# FPGA_SYSTERM.net
KiCad netlist of a schematic drawn in Altium Designer
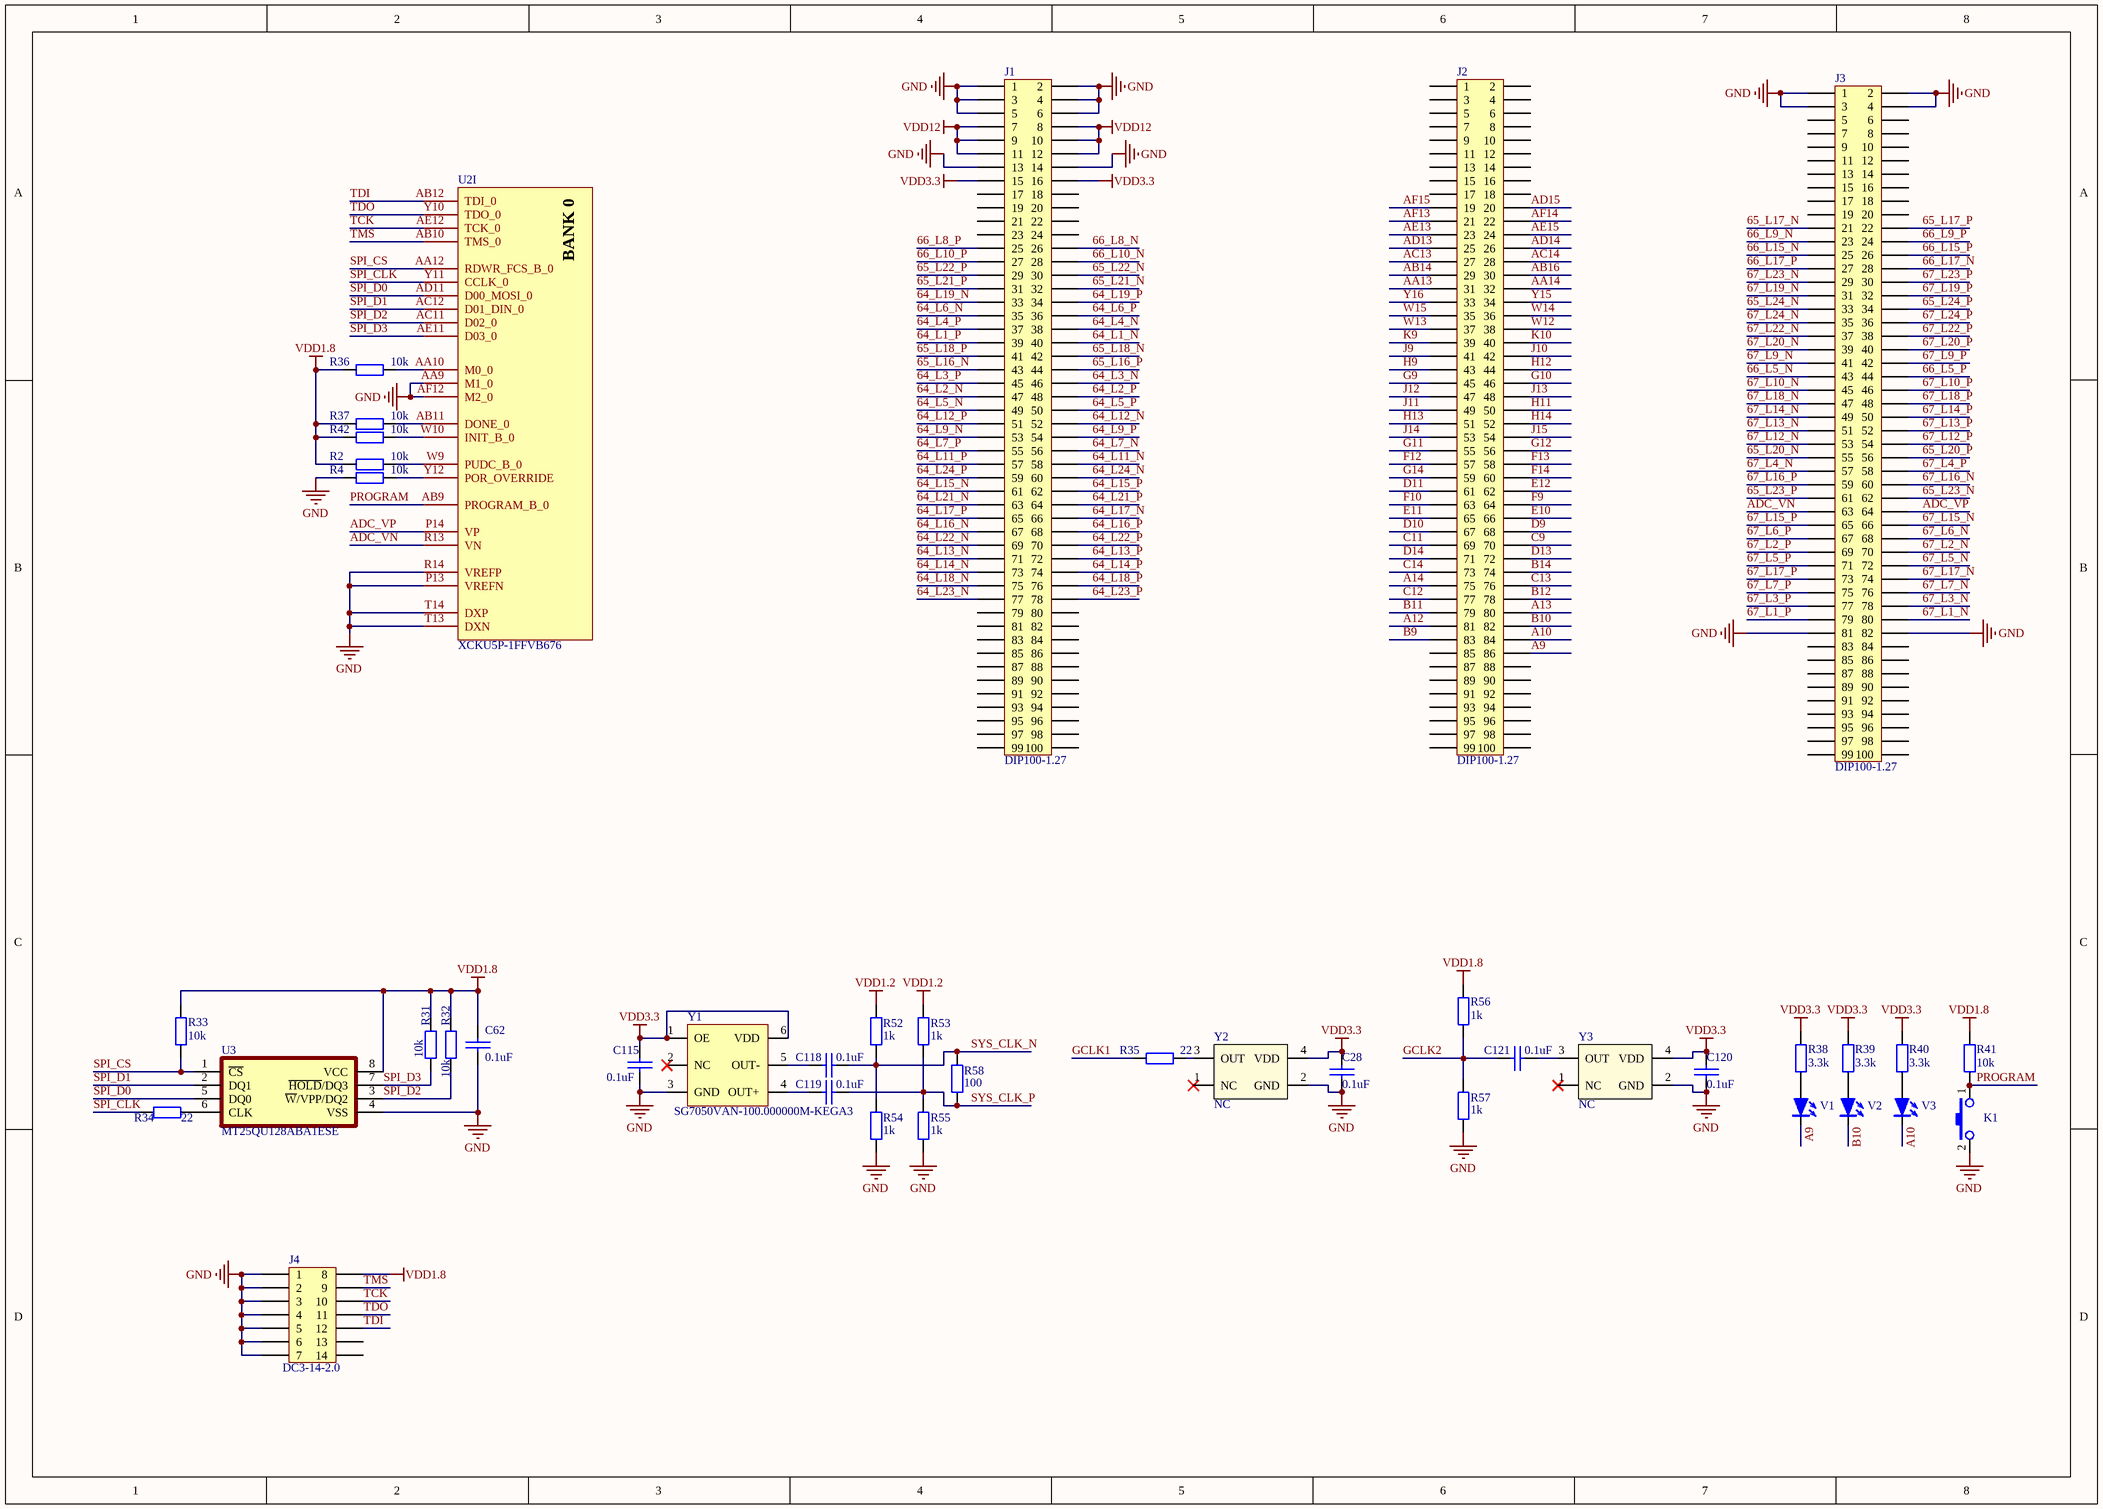
[diagram p0: FPGA SYSTERM.SchDoc]

(export (version "E")
  (design (tool "Eeschema 10.0.6"))
  (components
    (comp (ref "C28") (value "0.1uF") (footprint "0402_C_M") (libsource (lib "Component") (part "CAP")))
    (comp (ref "C62") (value "0.1uF") (footprint "0402_C_M") (libsource (lib "Component") (part "CAP")))
    (comp (ref "C115") (value "0.1uF") (footprint "0402_C_M") (libsource (lib "Component") (part "CAP")))
    (comp (ref "C118") (value "0.1uF") (footprint "0402_C_M") (libsource (lib "Component") (part "CAP")))
    (comp (ref "C119") (value "0.1uF") (footprint "0402_C_M") (libsource (lib "Component") (part "CAP")))
    (comp (ref "C120") (value "0.1uF") (footprint "0402_C_M") (libsource (lib "Component") (part "CAP")))
    (comp (ref "C121") (value "0.1uF") (footprint "0402_C_M") (libsource (lib "Component") (part "CAP")))
    (comp (ref "J1")
      (value "DIP100-1.27")
      (footprint "CON100_1.27")
      (libsource (lib "DIP_SIP") (part "CON100"))
    )
    (comp (ref "J2")
      (value "DIP100-1.27")
      (footprint "CON100_1.27")
      (libsource (lib "DIP_SIP") (part "CON100"))
    )
    (comp (ref "J3")
      (value "DIP100-1.27")
      (footprint "CON100_1.27")
      (libsource (lib "DIP_SIP") (part "CON100"))
    )
    (comp (ref "J4") (value "DC3-14-2.0") (footprint "DC3-14-2.0") (libsource (lib "DIP_SIP") (part "CON14")))
    (comp (ref "K1") (value "KEY") (footprint "KEY2") (libsource (lib "Common") (part "KEY1")))
    (comp (ref "R2") (value "10k") (footprint "0402_R_M") (libsource (lib "Common") (part "RES2")))
    (comp (ref "R4") (value "10k") (footprint "0402_R_M") (libsource (lib "Common") (part "RES2")))
    (comp (ref "R31") (value "10k") (footprint "0402_R_M") (libsource (lib "Common") (part "RES2")))
    (comp (ref "R32") (value "10k") (footprint "0402_R_M") (libsource (lib "Common") (part "RES2")))
    (comp (ref "R33") (value "10k") (footprint "0402_R_M") (libsource (lib "often") (part "RES2")))
    (comp (ref "R34") (value "22") (footprint "0402_R_M") (libsource (lib "Common") (part "RES2")))
    (comp (ref "R35") (value "22") (footprint "0402_R_M") (libsource (lib "Common") (part "RES2")))
    (comp (ref "R36") (value "10k") (footprint "0402_R_M") (libsource (lib "Common") (part "RES2")))
    (comp (ref "R37") (value "10k") (footprint "0402_R_M") (libsource (lib "Common") (part "RES2")))
    (comp (ref "R38") (value "3.3k") (footprint "0402_R_M") (libsource (lib "Common") (part "RES2")))
    (comp (ref "R39") (value "3.3k") (footprint "0402_R_M") (libsource (lib "Common") (part "RES2")))
    (comp (ref "R40") (value "3.3k") (footprint "0402_R_M") (libsource (lib "Common") (part "RES2")))
    (comp (ref "R41") (value "10k") (footprint "0402_R_M") (libsource (lib "Common") (part "RES2")))
    (comp (ref "R42") (value "10k") (footprint "0402_R_M") (libsource (lib "Common") (part "RES2")))
    (comp (ref "R52") (value "1k") (footprint "0402_R_M") (libsource (lib "Common") (part "RES2")))
    (comp (ref "R53") (value "1k") (footprint "0402_R_M") (libsource (lib "Common") (part "RES2")))
    (comp (ref "R54") (value "1k") (footprint "0402_R_M") (libsource (lib "Common") (part "RES2")))
    (comp (ref "R55") (value "1k") (footprint "0402_R_M") (libsource (lib "Common") (part "RES2")))
    (comp (ref "R56") (value "1k") (footprint "0402_R_M") (libsource (lib "Common") (part "RES2")))
    (comp (ref "R57") (value "1k") (footprint "0402_R_M") (libsource (lib "Common") (part "RES2")))
    (comp (ref "R58") (value "100") (footprint "0402_R_M") (libsource (lib "Common") (part "RES2")))
    (comp (ref "U2") (value "XCKU5P-1FFVB676") (libsource (lib "XCKU5P-FFVB676") (part "XCKU5P-FFVB676")))
    (comp (ref "U3")
      (value "MT25QU128ABA1ESE")
      (footprint "SOP8W")
      (libsource (lib "IC") (part "N25Q128A11EF840E"))
    )
    (comp (ref "V1") (value "LED") (footprint "0805D") (libsource (lib "发光管、数码管") (part "LED2")))
    (comp (ref "V2") (value "LED") (footprint "0805D") (libsource (lib "发光管、数码管") (part "LED2")))
    (comp (ref "V3") (value "LED") (footprint "0805D") (libsource (lib "发光管、数码管") (part "LED2")))
    (comp (ref "Y1")
      (value "SG7050VAN-100.000000M-KEGA3")
      (footprint "OSC 7050-6P")
      (libsource (lib "XCKU5P") (part "OB7050100MLDB6SI-00"))
    )
    (comp (ref "Y2") (value "NC") (footprint "OSC 7050-4P") (libsource (lib "XCKU5P") (part "XTAL")))
    (comp (ref "Y3") (value "NC") (footprint "OSC 7050-4P") (libsource (lib "XCKU5P") (part "XTAL")))
  )
  (nets
    (net (code "1") (name "/64_L1_N") (class "Default")
      (node (ref "J1") (pin "40") (pinfunction "40_40") (pintype "passive"))
    )
    (net (code "2") (name "/64_L1_P") (class "Default")
      (node (ref "J1") (pin "39") (pinfunction "39_39") (pintype "passive"))
    )
    (net (code "3") (name "/64_L2_N") (class "Default")
      (node (ref "J1") (pin "47") (pinfunction "47_47") (pintype "passive"))
    )
    (net (code "4") (name "/64_L2_P") (class "Default")
      (node (ref "J1") (pin "48") (pinfunction "48_48") (pintype "passive"))
    )
    (net (code "5") (name "/64_L3_N") (class "Default")
      (node (ref "J1") (pin "46") (pinfunction "46_46") (pintype "passive"))
    )
    (net (code "6") (name "/64_L3_P") (class "Default")
      (node (ref "J1") (pin "45") (pinfunction "45_45") (pintype "passive"))
    )
    (net (code "7") (name "/64_L4_N") (class "Default")
      (node (ref "J1") (pin "38") (pinfunction "38_38") (pintype "passive"))
    )
    (net (code "8") (name "/64_L4_P") (class "Default")
      (node (ref "J1") (pin "37") (pinfunction "37_37") (pintype "passive"))
    )
    (net (code "9") (name "/64_L5_N") (class "Default")
      (node (ref "J1") (pin "49") (pinfunction "49_49") (pintype "passive"))
    )
    (net (code "10") (name "/64_L5_P") (class "Default")
      (node (ref "J1") (pin "50") (pinfunction "50_50") (pintype "passive"))
    )
    (net (code "11") (name "/64_L6_N") (class "Default")
      (node (ref "J1") (pin "35") (pinfunction "35_35") (pintype "passive"))
    )
    (net (code "12") (name "/64_L6_P") (class "Default")
      (node (ref "J1") (pin "36") (pinfunction "36_36") (pintype "passive"))
    )
    (net (code "13") (name "/64_L7_N") (class "Default")
      (node (ref "J1") (pin "56") (pinfunction "56_56") (pintype "passive"))
    )
    (net (code "14") (name "/64_L7_P") (class "Default")
      (node (ref "J1") (pin "55") (pinfunction "55_55") (pintype "passive"))
    )
    (net (code "15") (name "/64_L9_N") (class "Default")
      (node (ref "J1") (pin "53") (pinfunction "53_53") (pintype "passive"))
    )
    (net (code "16") (name "/64_L9_P") (class "Default")
      (node (ref "J1") (pin "54") (pinfunction "54_54") (pintype "passive"))
    )
    (net (code "17") (name "/64_L11_N") (class "Default")
      (node (ref "J1") (pin "58") (pinfunction "58_58") (pintype "passive"))
    )
    (net (code "18") (name "/64_L11_P") (class "Default")
      (node (ref "J1") (pin "57") (pinfunction "57_57") (pintype "passive"))
    )
    (net (code "19") (name "/64_L12_N") (class "Default")
      (node (ref "J1") (pin "52") (pinfunction "52_52") (pintype "passive"))
    )
    (net (code "20") (name "/64_L12_P") (class "Default")
      (node (ref "J1") (pin "51") (pinfunction "51_51") (pintype "passive"))
    )
    (net (code "21") (name "/64_L13_N") (class "Default")
      (node (ref "J1") (pin "71") (pinfunction "71_71") (pintype "passive"))
    )
    (net (code "22") (name "/64_L13_P") (class "Default")
      (node (ref "J1") (pin "72") (pinfunction "72_72") (pintype "passive"))
    )
    (net (code "23") (name "/64_L14_N") (class "Default")
      (node (ref "J1") (pin "73") (pinfunction "73_73") (pintype "passive"))
    )
    (net (code "24") (name "/64_L14_P") (class "Default")
      (node (ref "J1") (pin "74") (pinfunction "74_74") (pintype "passive"))
    )
    (net (code "25") (name "/64_L15_N") (class "Default")
      (node (ref "J1") (pin "61") (pinfunction "61_61") (pintype "passive"))
    )
    (net (code "26") (name "/64_L15_P") (class "Default")
      (node (ref "J1") (pin "62") (pinfunction "62_62") (pintype "passive"))
    )
    (net (code "27") (name "/64_L16_N") (class "Default")
      (node (ref "J1") (pin "67") (pinfunction "67_67") (pintype "passive"))
    )
    (net (code "28") (name "/64_L16_P") (class "Default")
      (node (ref "J1") (pin "68") (pinfunction "68_68") (pintype "passive"))
    )
    (net (code "29") (name "/64_L17_N") (class "Default")
      (node (ref "J1") (pin "66") (pinfunction "66_66") (pintype "passive"))
    )
    (net (code "30") (name "/64_L17_P") (class "Default")
      (node (ref "J1") (pin "65") (pinfunction "65_65") (pintype "passive"))
    )
    (net (code "31") (name "/64_L18_N") (class "Default")
      (node (ref "J1") (pin "75") (pinfunction "75_75") (pintype "passive"))
    )
    (net (code "32") (name "/64_L18_P") (class "Default")
      (node (ref "J1") (pin "76") (pinfunction "76_76") (pintype "passive"))
    )
    (net (code "33") (name "/64_L19_N") (class "Default")
      (node (ref "J1") (pin "33") (pinfunction "33_33") (pintype "passive"))
    )
    (net (code "34") (name "/64_L19_P") (class "Default")
      (node (ref "J1") (pin "34") (pinfunction "34_34") (pintype "passive"))
    )
    (net (code "35") (name "/64_L21_N") (class "Default")
      (node (ref "J1") (pin "63") (pinfunction "63_63") (pintype "passive"))
    )
    (net (code "36") (name "/64_L21_P") (class "Default")
      (node (ref "J1") (pin "64") (pinfunction "64_64") (pintype "passive"))
    )
    (net (code "37") (name "/64_L22_N") (class "Default")
      (node (ref "J1") (pin "69") (pinfunction "69_69") (pintype "passive"))
    )
    (net (code "38") (name "/64_L22_P") (class "Default")
      (node (ref "J1") (pin "70") (pinfunction "70_70") (pintype "passive"))
    )
    (net (code "39") (name "/64_L23_N") (class "Default")
      (node (ref "J1") (pin "77") (pinfunction "77_77") (pintype "passive"))
    )
    (net (code "40") (name "/64_L23_P") (class "Default")
      (node (ref "J1") (pin "78") (pinfunction "78_78") (pintype "passive"))
    )
    (net (code "41") (name "/64_L24_N") (class "Default")
      (node (ref "J1") (pin "60") (pinfunction "60_60") (pintype "passive"))
    )
    (net (code "42") (name "/64_L24_P") (class "Default")
      (node (ref "J1") (pin "59") (pinfunction "59_59") (pintype "passive"))
    )
    (net (code "43") (name "/65_L16_N") (class "Default")
      (node (ref "J1") (pin "43") (pinfunction "43_43") (pintype "passive"))
    )
    (net (code "44") (name "/65_L16_P") (class "Default")
      (node (ref "J1") (pin "44") (pinfunction "44_44") (pintype "passive"))
    )
    (net (code "45") (name "/65_L17_N") (class "Default")
      (node (ref "J3") (pin "21") (pinfunction "21_21") (pintype "passive"))
    )
    (net (code "46") (name "/65_L17_P") (class "Default")
      (node (ref "J3") (pin "22") (pinfunction "22_22") (pintype "passive"))
    )
    (net (code "47") (name "/65_L18_N") (class "Default")
      (node (ref "J1") (pin "42") (pinfunction "42_42") (pintype "passive"))
    )
    (net (code "48") (name "/65_L18_P") (class "Default")
      (node (ref "J1") (pin "41") (pinfunction "41_41") (pintype "passive"))
    )
    (net (code "49") (name "/65_L20_N") (class "Default")
      (node (ref "J3") (pin "55") (pinfunction "55_55") (pintype "passive"))
    )
    (net (code "50") (name "/65_L20_P") (class "Default")
      (node (ref "J3") (pin "56") (pinfunction "56_56") (pintype "passive"))
    )
    (net (code "51") (name "/65_L21_N") (class "Default")
      (node (ref "J1") (pin "32") (pinfunction "32_32") (pintype "passive"))
    )
    (net (code "52") (name "/65_L21_P") (class "Default")
      (node (ref "J1") (pin "31") (pinfunction "31_31") (pintype "passive"))
    )
    (net (code "53") (name "/65_L22_N") (class "Default")
      (node (ref "J1") (pin "30") (pinfunction "30_30") (pintype "passive"))
    )
    (net (code "54") (name "/65_L22_P") (class "Default")
      (node (ref "J1") (pin "29") (pinfunction "29_29") (pintype "passive"))
    )
    (net (code "55") (name "/65_L23_N") (class "Default")
      (node (ref "J3") (pin "62") (pinfunction "62_62") (pintype "passive"))
    )
    (net (code "56") (name "/65_L23_P") (class "Default")
      (node (ref "J3") (pin "61") (pinfunction "61_61") (pintype "passive"))
    )
    (net (code "57") (name "/65_L24_N") (class "Default")
      (node (ref "J3") (pin "33") (pinfunction "33_33") (pintype "passive"))
    )
    (net (code "58") (name "/65_L24_P") (class "Default")
      (node (ref "J3") (pin "34") (pinfunction "34_34") (pintype "passive"))
    )
    (net (code "59") (name "/66_L5_N") (class "Default")
      (node (ref "J3") (pin "43") (pinfunction "43_43") (pintype "passive"))
    )
    (net (code "60") (name "/66_L5_P") (class "Default")
      (node (ref "J3") (pin "44") (pinfunction "44_44") (pintype "passive"))
    )
    (net (code "61") (name "/66_L8_N") (class "Default")
      (node (ref "J1") (pin "26") (pinfunction "26_26") (pintype "passive"))
    )
    (net (code "62") (name "/66_L8_P") (class "Default")
      (node (ref "J1") (pin "25") (pinfunction "25_25") (pintype "passive"))
    )
    (net (code "63") (name "/66_L9_N") (class "Default")
      (node (ref "J3") (pin "23") (pinfunction "23_23") (pintype "passive"))
    )
    (net (code "64") (name "/66_L9_P") (class "Default")
      (node (ref "J3") (pin "24") (pinfunction "24_24") (pintype "passive"))
    )
    (net (code "65") (name "/66_L10_N") (class "Default")
      (node (ref "J1") (pin "28") (pinfunction "28_28") (pintype "passive"))
    )
    (net (code "66") (name "/66_L10_P") (class "Default")
      (node (ref "J1") (pin "27") (pinfunction "27_27") (pintype "passive"))
    )
    (net (code "67") (name "/66_L15_N") (class "Default")
      (node (ref "J3") (pin "25") (pinfunction "25_25") (pintype "passive"))
    )
    (net (code "68") (name "/66_L15_P") (class "Default")
      (node (ref "J3") (pin "26") (pinfunction "26_26") (pintype "passive"))
    )
    (net (code "69") (name "/66_L17_N") (class "Default")
      (node (ref "J3") (pin "28") (pinfunction "28_28") (pintype "passive"))
    )
    (net (code "70") (name "/66_L17_P") (class "Default")
      (node (ref "J3") (pin "27") (pinfunction "27_27") (pintype "passive"))
    )
    (net (code "71") (name "/67_L1_N") (class "Default")
      (node (ref "J3") (pin "80") (pinfunction "80_80") (pintype "passive"))
    )
    (net (code "72") (name "/67_L1_P") (class "Default")
      (node (ref "J3") (pin "79") (pinfunction "79_79") (pintype "passive"))
    )
    (net (code "73") (name "/67_L2_N") (class "Default")
      (node (ref "J3") (pin "70") (pinfunction "70_70") (pintype "passive"))
    )
    (net (code "74") (name "/67_L2_P") (class "Default")
      (node (ref "J3") (pin "69") (pinfunction "69_69") (pintype "passive"))
    )
    (net (code "75") (name "/67_L3_N") (class "Default")
      (node (ref "J3") (pin "78") (pinfunction "78_78") (pintype "passive"))
    )
    (net (code "76") (name "/67_L3_P") (class "Default")
      (node (ref "J3") (pin "77") (pinfunction "77_77") (pintype "passive"))
    )
    (net (code "77") (name "/67_L4_N") (class "Default")
      (node (ref "J3") (pin "57") (pinfunction "57_57") (pintype "passive"))
    )
    (net (code "78") (name "/67_L4_P") (class "Default")
      (node (ref "J3") (pin "58") (pinfunction "58_58") (pintype "passive"))
    )
    (net (code "79") (name "/67_L5_N") (class "Default")
      (node (ref "J3") (pin "72") (pinfunction "72_72") (pintype "passive"))
    )
    (net (code "80") (name "/67_L5_P") (class "Default")
      (node (ref "J3") (pin "71") (pinfunction "71_71") (pintype "passive"))
    )
    (net (code "81") (name "/67_L6_N") (class "Default")
      (node (ref "J3") (pin "68") (pinfunction "68_68") (pintype "passive"))
    )
    (net (code "82") (name "/67_L6_P") (class "Default")
      (node (ref "J3") (pin "67") (pinfunction "67_67") (pintype "passive"))
    )
    (net (code "83") (name "/67_L7_N") (class "Default")
      (node (ref "J3") (pin "76") (pinfunction "76_76") (pintype "passive"))
    )
    (net (code "84") (name "/67_L7_P") (class "Default")
      (node (ref "J3") (pin "75") (pinfunction "75_75") (pintype "passive"))
    )
    (net (code "85") (name "/67_L9_N") (class "Default")
      (node (ref "J3") (pin "41") (pinfunction "41_41") (pintype "passive"))
    )
    (net (code "86") (name "/67_L9_P") (class "Default")
      (node (ref "J3") (pin "42") (pinfunction "42_42") (pintype "passive"))
    )
    (net (code "87") (name "/67_L10_N") (class "Default")
      (node (ref "J3") (pin "45") (pinfunction "45_45") (pintype "passive"))
    )
    (net (code "88") (name "/67_L10_P") (class "Default")
      (node (ref "J3") (pin "46") (pinfunction "46_46") (pintype "passive"))
    )
    (net (code "89") (name "/67_L12_N") (class "Default")
      (node (ref "J3") (pin "53") (pinfunction "53_53") (pintype "passive"))
    )
    (net (code "90") (name "/67_L12_P") (class "Default")
      (node (ref "J3") (pin "54") (pinfunction "54_54") (pintype "passive"))
    )
    (net (code "91") (name "/67_L13_N") (class "Default")
      (node (ref "J3") (pin "51") (pinfunction "51_51") (pintype "passive"))
    )
    (net (code "92") (name "/67_L13_P") (class "Default")
      (node (ref "J3") (pin "52") (pinfunction "52_52") (pintype "passive"))
    )
    (net (code "93") (name "/67_L14_N") (class "Default")
      (node (ref "J3") (pin "49") (pinfunction "49_49") (pintype "passive"))
    )
    (net (code "94") (name "/67_L14_P") (class "Default")
      (node (ref "J3") (pin "50") (pinfunction "50_50") (pintype "passive"))
    )
    (net (code "95") (name "/67_L15_N") (class "Default")
      (node (ref "J3") (pin "66") (pinfunction "66_66") (pintype "passive"))
    )
    (net (code "96") (name "/67_L15_P") (class "Default")
      (node (ref "J3") (pin "65") (pinfunction "65_65") (pintype "passive"))
    )
    (net (code "97") (name "/67_L16_N") (class "Default")
      (node (ref "J3") (pin "60") (pinfunction "60_60") (pintype "passive"))
    )
    (net (code "98") (name "/67_L16_P") (class "Default")
      (node (ref "J3") (pin "59") (pinfunction "59_59") (pintype "passive"))
    )
    (net (code "99") (name "/67_L17_N") (class "Default")
      (node (ref "J3") (pin "74") (pinfunction "74_74") (pintype "passive"))
    )
    (net (code "100") (name "/67_L17_P") (class "Default")
      (node (ref "J3") (pin "73") (pinfunction "73_73") (pintype "passive"))
    )
    (net (code "101") (name "/67_L18_N") (class "Default")
      (node (ref "J3") (pin "47") (pinfunction "47_47") (pintype "passive"))
    )
    (net (code "102") (name "/67_L18_P") (class "Default")
      (node (ref "J3") (pin "48") (pinfunction "48_48") (pintype "passive"))
    )
    (net (code "103") (name "/67_L19_N") (class "Default")
      (node (ref "J3") (pin "31") (pinfunction "31_31") (pintype "passive"))
    )
    (net (code "104") (name "/67_L19_P") (class "Default")
      (node (ref "J3") (pin "32") (pinfunction "32_32") (pintype "passive"))
    )
    (net (code "105") (name "/67_L20_N") (class "Default")
      (node (ref "J3") (pin "39") (pinfunction "39_39") (pintype "passive"))
    )
    (net (code "106") (name "/67_L20_P") (class "Default")
      (node (ref "J3") (pin "40") (pinfunction "40_40") (pintype "passive"))
    )
    (net (code "107") (name "/67_L22_N") (class "Default")
      (node (ref "J3") (pin "37") (pinfunction "37_37") (pintype "passive"))
    )
    (net (code "108") (name "/67_L22_P") (class "Default")
      (node (ref "J3") (pin "38") (pinfunction "38_38") (pintype "passive"))
    )
    (net (code "109") (name "/67_L23_N") (class "Default")
      (node (ref "J3") (pin "29") (pinfunction "29_29") (pintype "passive"))
    )
    (net (code "110") (name "/67_L23_P") (class "Default")
      (node (ref "J3") (pin "30") (pinfunction "30_30") (pintype "passive"))
    )
    (net (code "111") (name "/67_L24_N") (class "Default")
      (node (ref "J3") (pin "35") (pinfunction "35_35") (pintype "passive"))
    )
    (net (code "112") (name "/67_L24_P") (class "Default")
      (node (ref "J3") (pin "36") (pinfunction "36_36") (pintype "passive"))
    )
    (net (code "113") (name "/A9") (class "Default")
      (node (ref "J2") (pin "86") (pinfunction "86_86") (pintype "passive"))
      (node (ref "V1") (pin "2") (pinfunction "2_2") (pintype "passive"))
    )
    (net (code "114") (name "/A10") (class "Default")
      (node (ref "J2") (pin "84") (pinfunction "84_84") (pintype "passive"))
      (node (ref "V3") (pin "2") (pinfunction "2_2") (pintype "passive"))
    )
    (net (code "115") (name "/A12") (class "Default")
      (node (ref "J2") (pin "81") (pinfunction "81_81") (pintype "passive"))
    )
    (net (code "116") (name "/A13") (class "Default")
      (node (ref "J2") (pin "80") (pinfunction "80_80") (pintype "passive"))
    )
    (net (code "117") (name "/A14") (class "Default")
      (node (ref "J2") (pin "75") (pinfunction "75_75") (pintype "passive"))
    )
    (net (code "118") (name "/AA13") (class "Default")
      (node (ref "J2") (pin "31") (pinfunction "31_31") (pintype "passive"))
    )
    (net (code "119") (name "/AA14") (class "Default")
      (node (ref "J2") (pin "32") (pinfunction "32_32") (pintype "passive"))
    )
    (net (code "120") (name "/AB14") (class "Default")
      (node (ref "J2") (pin "29") (pinfunction "29_29") (pintype "passive"))
    )
    (net (code "121") (name "/AB16") (class "Default")
      (node (ref "J2") (pin "30") (pinfunction "30_30") (pintype "passive"))
    )
    (net (code "122") (name "/AC13") (class "Default")
      (node (ref "J2") (pin "27") (pinfunction "27_27") (pintype "passive"))
    )
    (net (code "123") (name "/AC14") (class "Default")
      (node (ref "J2") (pin "28") (pinfunction "28_28") (pintype "passive"))
    )
    (net (code "124") (name "/AD13") (class "Default")
      (node (ref "J2") (pin "25") (pinfunction "25_25") (pintype "passive"))
    )
    (net (code "125") (name "/AD14") (class "Default")
      (node (ref "J2") (pin "26") (pinfunction "26_26") (pintype "passive"))
    )
    (net (code "126") (name "/AD15") (class "Default")
      (node (ref "J2") (pin "20") (pinfunction "20_20") (pintype "passive"))
    )
    (net (code "127") (name "/ADC_VN") (class "Default")
      (node (ref "J3") (pin "63") (pinfunction "63_63") (pintype "passive"))
      (node (ref "U2") (pin "R13") (pinfunction "VN_R13") (pintype "passive"))
    )
    (net (code "128") (name "/ADC_VP") (class "Default")
      (node (ref "J3") (pin "64") (pinfunction "64_64") (pintype "passive"))
      (node (ref "U2") (pin "P14") (pinfunction "VP_P14") (pintype "passive"))
    )
    (net (code "129") (name "/AE13") (class "Default")
      (node (ref "J2") (pin "23") (pinfunction "23_23") (pintype "passive"))
    )
    (net (code "130") (name "/AE15") (class "Default")
      (node (ref "J2") (pin "24") (pinfunction "24_24") (pintype "passive"))
    )
    (net (code "131") (name "/AF13") (class "Default")
      (node (ref "J2") (pin "21") (pinfunction "21_21") (pintype "passive"))
    )
    (net (code "132") (name "/AF14") (class "Default")
      (node (ref "J2") (pin "22") (pinfunction "22_22") (pintype "passive"))
    )
    (net (code "133") (name "/AF15") (class "Default")
      (node (ref "J2") (pin "19") (pinfunction "19_19") (pintype "passive"))
    )
    (net (code "134") (name "/B9") (class "Default")
      (node (ref "J2") (pin "83") (pinfunction "83_83") (pintype "passive"))
    )
    (net (code "135") (name "/B10") (class "Default")
      (node (ref "J2") (pin "82") (pinfunction "82_82") (pintype "passive"))
      (node (ref "V2") (pin "2") (pinfunction "2_2") (pintype "passive"))
    )
    (net (code "136") (name "/B11") (class "Default")
      (node (ref "J2") (pin "79") (pinfunction "79_79") (pintype "passive"))
    )
    (net (code "137") (name "/B12") (class "Default")
      (node (ref "J2") (pin "78") (pinfunction "78_78") (pintype "passive"))
    )
    (net (code "138") (name "/B14") (class "Default")
      (node (ref "J2") (pin "74") (pinfunction "74_74") (pintype "passive"))
    )
    (net (code "139") (name "/C9") (class "Default")
      (node (ref "J2") (pin "70") (pinfunction "70_70") (pintype "passive"))
    )
    (net (code "140") (name "/C11") (class "Default")
      (node (ref "J2") (pin "69") (pinfunction "69_69") (pintype "passive"))
    )
    (net (code "141") (name "/C12") (class "Default")
      (node (ref "J2") (pin "77") (pinfunction "77_77") (pintype "passive"))
    )
    (net (code "142") (name "/C13") (class "Default")
      (node (ref "J2") (pin "76") (pinfunction "76_76") (pintype "passive"))
    )
    (net (code "143") (name "/C14") (class "Default")
      (node (ref "J2") (pin "73") (pinfunction "73_73") (pintype "passive"))
    )
    (net (code "144") (name "/D9") (class "Default")
      (node (ref "J2") (pin "68") (pinfunction "68_68") (pintype "passive"))
    )
    (net (code "145") (name "/D10") (class "Default")
      (node (ref "J2") (pin "67") (pinfunction "67_67") (pintype "passive"))
    )
    (net (code "146") (name "/D11") (class "Default")
      (node (ref "J2") (pin "61") (pinfunction "61_61") (pintype "passive"))
    )
    (net (code "147") (name "/D13") (class "Default")
      (node (ref "J2") (pin "72") (pinfunction "72_72") (pintype "passive"))
    )
    (net (code "148") (name "/D14") (class "Default")
      (node (ref "J2") (pin "71") (pinfunction "71_71") (pintype "passive"))
    )
    (net (code "149") (name "/E10") (class "Default")
      (node (ref "J2") (pin "66") (pinfunction "66_66") (pintype "passive"))
    )
    (net (code "150") (name "/E11") (class "Default")
      (node (ref "J2") (pin "65") (pinfunction "65_65") (pintype "passive"))
    )
    (net (code "151") (name "/E12") (class "Default")
      (node (ref "J2") (pin "62") (pinfunction "62_62") (pintype "passive"))
    )
    (net (code "152") (name "/F9") (class "Default")
      (node (ref "J2") (pin "64") (pinfunction "64_64") (pintype "passive"))
    )
    (net (code "153") (name "/F10") (class "Default")
      (node (ref "J2") (pin "63") (pinfunction "63_63") (pintype "passive"))
    )
    (net (code "154") (name "/F12") (class "Default")
      (node (ref "J2") (pin "57") (pinfunction "57_57") (pintype "passive"))
    )
    (net (code "155") (name "/F13") (class "Default")
      (node (ref "J2") (pin "58") (pinfunction "58_58") (pintype "passive"))
    )
    (net (code "156") (name "/F14") (class "Default")
      (node (ref "J2") (pin "60") (pinfunction "60_60") (pintype "passive"))
    )
    (net (code "157") (name "/G9") (class "Default")
      (node (ref "J2") (pin "45") (pinfunction "45_45") (pintype "passive"))
    )
    (net (code "158") (name "/G10") (class "Default")
      (node (ref "J2") (pin "46") (pinfunction "46_46") (pintype "passive"))
    )
    (net (code "159") (name "/G11") (class "Default")
      (node (ref "J2") (pin "55") (pinfunction "55_55") (pintype "passive"))
    )
    (net (code "160") (name "/G12") (class "Default")
      (node (ref "J2") (pin "56") (pinfunction "56_56") (pintype "passive"))
    )
    (net (code "161") (name "/G14") (class "Default")
      (node (ref "J2") (pin "59") (pinfunction "59_59") (pintype "passive"))
    )
    (net (code "162") (name "/GCLK1") (class "Default") (node (ref "R35") (pin "2") (pintype "passive")))
    (net (code "163") (name "/GCLK2") (class "Default")
      (node (ref "C121") (pin "1") (pinfunction "1_1") (pintype "passive"))
      (node (ref "R56") (pin "2") (pintype "passive"))
      (node (ref "R57") (pin "1") (pintype "passive"))
    )
    (net (code "164") (name "/H9") (class "Default")
      (node (ref "J2") (pin "43") (pinfunction "43_43") (pintype "passive"))
    )
    (net (code "165") (name "/H11") (class "Default")
      (node (ref "J2") (pin "50") (pinfunction "50_50") (pintype "passive"))
    )
    (net (code "166") (name "/H12") (class "Default")
      (node (ref "J2") (pin "44") (pinfunction "44_44") (pintype "passive"))
    )
    (net (code "167") (name "/H13") (class "Default")
      (node (ref "J2") (pin "51") (pinfunction "51_51") (pintype "passive"))
    )
    (net (code "168") (name "/H14") (class "Default")
      (node (ref "J2") (pin "52") (pinfunction "52_52") (pintype "passive"))
    )
    (net (code "169") (name "/J9") (class "Default")
      (node (ref "J2") (pin "41") (pinfunction "41_41") (pintype "passive"))
    )
    (net (code "170") (name "/J10") (class "Default")
      (node (ref "J2") (pin "42") (pinfunction "42_42") (pintype "passive"))
    )
    (net (code "171") (name "/J11") (class "Default")
      (node (ref "J2") (pin "49") (pinfunction "49_49") (pintype "passive"))
    )
    (net (code "172") (name "/J12") (class "Default")
      (node (ref "J2") (pin "47") (pinfunction "47_47") (pintype "passive"))
    )
    (net (code "173") (name "/J13") (class "Default")
      (node (ref "J2") (pin "48") (pinfunction "48_48") (pintype "passive"))
    )
    (net (code "174") (name "/J14") (class "Default")
      (node (ref "J2") (pin "53") (pinfunction "53_53") (pintype "passive"))
    )
    (net (code "175") (name "/J15") (class "Default")
      (node (ref "J2") (pin "54") (pinfunction "54_54") (pintype "passive"))
    )
    (net (code "176") (name "/K9") (class "Default")
      (node (ref "J2") (pin "39") (pinfunction "39_39") (pintype "passive"))
    )
    (net (code "177") (name "/K10") (class "Default")
      (node (ref "J2") (pin "40") (pinfunction "40_40") (pintype "passive"))
    )
    (net (code "178") (name "/PROGRAM") (class "Default")
      (node (ref "K1") (pin "1") (pintype "passive"))
      (node (ref "R41") (pin "1") (pintype "passive"))
      (node (ref "U2") (pin "AB9") (pinfunction "PROGRAM_B_0_AB9") (pintype "passive"))
    )
    (net (code "179") (name "/SPI_CLK") (class "Default")
      (node (ref "R34") (pin "2") (pintype "passive"))
      (node (ref "U2") (pin "Y11") (pinfunction "CCLK_0_Y11") (pintype "passive"))
    )
    (net (code "180") (name "/SPI_CS") (class "Default")
      (node (ref "R33") (pin "2") (pintype "passive"))
      (node (ref "U2") (pin "AA12") (pinfunction "RDWR_FCS_B_0_AA12") (pintype "passive"))
      (node (ref "U3") (pin "1") (pinfunction "~{CS}_1") (pintype "passive"))
    )
    (net (code "181") (name "/SPI_D0") (class "Default")
      (node (ref "U2") (pin "AD11") (pinfunction "D00_MOSI_0_AD11") (pintype "passive"))
      (node (ref "U3") (pin "5") (pinfunction "DQ0_5") (pintype "passive"))
    )
    (net (code "182") (name "/SPI_D1") (class "Default")
      (node (ref "U2") (pin "AC12") (pinfunction "D01_DIN_0_AC12") (pintype "passive"))
      (node (ref "U3") (pin "2") (pinfunction "DQ1_2") (pintype "passive"))
    )
    (net (code "183") (name "/SPI_D2") (class "Default")
      (node (ref "R32") (pin "1") (pintype "passive"))
      (node (ref "U2") (pin "AC11") (pinfunction "D02_0_AC11") (pintype "passive"))
      (node (ref "U3") (pin "3") (pinfunction "~{W}/VPP/DQ2_3") (pintype "passive"))
    )
    (net (code "184") (name "/SPI_D3") (class "Default")
      (node (ref "R31") (pin "1") (pintype "passive"))
      (node (ref "U2") (pin "AE11") (pinfunction "D03_0_AE11") (pintype "passive"))
      (node (ref "U3") (pin "7") (pinfunction "~{HOLD}/DQ3_7") (pintype "passive"))
    )
    (net (code "185") (name "/SYS_CLK_N") (class "Default")
      (node (ref "C118") (pin "2") (pinfunction "2_2") (pintype "passive"))
      (node (ref "R52") (pin "2") (pintype "passive"))
      (node (ref "R54") (pin "1") (pintype "passive"))
      (node (ref "R58") (pin "1") (pintype "passive"))
    )
    (net (code "186") (name "/SYS_CLK_P") (class "Default")
      (node (ref "C119") (pin "2") (pinfunction "2_2") (pintype "passive"))
      (node (ref "R53") (pin "2") (pintype "passive"))
      (node (ref "R55") (pin "1") (pintype "passive"))
      (node (ref "R58") (pin "2") (pintype "passive"))
    )
    (net (code "187") (name "/TCK") (class "Default")
      (node (ref "J4") (pin "10") (pinfunction "10_10") (pintype "passive"))
      (node (ref "U2") (pin "AE12") (pinfunction "TCK_0_AE12") (pintype "passive"))
    )
    (net (code "188") (name "/TDI") (class "Default")
      (node (ref "J4") (pin "12") (pinfunction "12_12") (pintype "passive"))
      (node (ref "U2") (pin "AB12") (pinfunction "TDI_0_AB12") (pintype "passive"))
    )
    (net (code "189") (name "/TDO") (class "Default")
      (node (ref "J4") (pin "11") (pinfunction "11_11") (pintype "passive"))
      (node (ref "U2") (pin "Y10") (pinfunction "TDO_0_Y10") (pintype "passive"))
    )
    (net (code "190") (name "/TMS") (class "Default")
      (node (ref "J4") (pin "9") (pinfunction "9_9") (pintype "passive"))
      (node (ref "U2") (pin "AB10") (pinfunction "TMS_0_AB10") (pintype "passive"))
    )
    (net (code "191") (name "/W12") (class "Default")
      (node (ref "J2") (pin "38") (pinfunction "38_38") (pintype "passive"))
    )
    (net (code "192") (name "/W13") (class "Default")
      (node (ref "J2") (pin "37") (pinfunction "37_37") (pintype "passive"))
    )
    (net (code "193") (name "/W14") (class "Default")
      (node (ref "J2") (pin "36") (pinfunction "36_36") (pintype "passive"))
    )
    (net (code "194") (name "/W15") (class "Default")
      (node (ref "J2") (pin "35") (pinfunction "35_35") (pintype "passive"))
    )
    (net (code "195") (name "/Y15") (class "Default")
      (node (ref "J2") (pin "34") (pinfunction "34_34") (pintype "passive"))
    )
    (net (code "196") (name "/Y16") (class "Default")
      (node (ref "J2") (pin "33") (pinfunction "33_33") (pintype "passive"))
    )
    (net (code "197") (name "GND") (class "Default")
      (node (ref "C115") (pin "2") (pinfunction "2_2") (pintype "passive"))
      (node (ref "C120") (pin "2") (pinfunction "2_2") (pintype "passive"))
      (node (ref "C28") (pin "2") (pinfunction "2_2") (pintype "passive"))
      (node (ref "C62") (pin "2") (pinfunction "2_2") (pintype "passive"))
      (node (ref "J1") (pin "1") (pinfunction "1_1") (pintype "passive"))
      (node (ref "J1") (pin "13") (pinfunction "13_13") (pintype "passive"))
      (node (ref "J1") (pin "14") (pinfunction "14_14") (pintype "passive"))
      (node (ref "J1") (pin "2") (pinfunction "2_2") (pintype "passive"))
      (node (ref "J1") (pin "3") (pinfunction "3_3") (pintype "passive"))
      (node (ref "J1") (pin "4") (pinfunction "4_4") (pintype "passive"))
      (node (ref "J1") (pin "5") (pinfunction "5_5") (pintype "passive"))
      (node (ref "J1") (pin "6") (pinfunction "6_6") (pintype "passive"))
      (node (ref "J3") (pin "1") (pinfunction "1_1") (pintype "passive"))
      (node (ref "J3") (pin "2") (pinfunction "2_2") (pintype "passive"))
      (node (ref "J3") (pin "3") (pinfunction "3_3") (pintype "passive"))
      (node (ref "J3") (pin "4") (pinfunction "4_4") (pintype "passive"))
      (node (ref "J3") (pin "81") (pinfunction "81_81") (pintype "passive"))
      (node (ref "J3") (pin "82") (pinfunction "82_82") (pintype "passive"))
      (node (ref "J4") (pin "1") (pinfunction "1_1") (pintype "passive"))
      (node (ref "J4") (pin "2") (pinfunction "2_2") (pintype "passive"))
      (node (ref "J4") (pin "3") (pinfunction "3_3") (pintype "passive"))
      (node (ref "J4") (pin "4") (pinfunction "4_4") (pintype "passive"))
      (node (ref "J4") (pin "5") (pinfunction "5_5") (pintype "passive"))
      (node (ref "J4") (pin "6") (pinfunction "6_6") (pintype "passive"))
      (node (ref "J4") (pin "7") (pinfunction "7_7") (pintype "passive"))
      (node (ref "K1") (pin "2") (pintype "passive"))
      (node (ref "R4") (pin "2") (pintype "passive"))
      (node (ref "R54") (pin "2") (pintype "passive"))
      (node (ref "R55") (pin "2") (pintype "passive"))
      (node (ref "R57") (pin "2") (pintype "passive"))
      (node (ref "U2") (pin "AA9") (pinfunction "M1_0_AA9") (pintype "passive"))
      (node (ref "U2") (pin "AF12") (pinfunction "M2_0_AF12") (pintype "passive"))
      (node (ref "U2") (pin "P13") (pinfunction "VREFN_P13") (pintype "passive"))
      (node (ref "U2") (pin "R14") (pinfunction "VREFP_R14") (pintype "passive"))
      (node (ref "U2") (pin "T13") (pinfunction "DXN_T13") (pintype "passive"))
      (node (ref "U2") (pin "T14") (pinfunction "DXP_T14") (pintype "passive"))
      (node (ref "U3") (pin "4") (pinfunction "VSS_4") (pintype "passive"))
      (node (ref "Y1") (pin "3") (pinfunction "GND_3") (pintype "passive"))
      (node (ref "Y2") (pin "2") (pinfunction "GND_2") (pintype "passive"))
      (node (ref "Y3") (pin "2") (pinfunction "GND_2") (pintype "passive"))
    )
    (net (code "198") (name "Net-(R38-Pad1)") (class "Default")
      (node (ref "R38") (pin "1") (pintype "passive"))
      (node (ref "V1") (pin "1") (pinfunction "1_1") (pintype "passive"))
    )
    (net (code "199") (name "Net-(R39-Pad1)") (class "Default")
      (node (ref "R39") (pin "1") (pintype "passive"))
      (node (ref "V2") (pin "1") (pinfunction "1_1") (pintype "passive"))
    )
    (net (code "200") (name "Net-(R40-Pad1)") (class "Default")
      (node (ref "R40") (pin "1") (pintype "passive"))
      (node (ref "V3") (pin "1") (pinfunction "1_1") (pintype "passive"))
    )
    (net (code "201") (name "Net-(U2I-DONE_0)") (class "Default")
      (node (ref "R37") (pin "1") (pintype "passive"))
      (node (ref "U2") (pin "AB11") (pinfunction "DONE_0_AB11") (pintype "passive"))
    )
    (net (code "202") (name "Net-(U2I-INIT_B_0)") (class "Default")
      (node (ref "R42") (pin "1") (pintype "passive"))
      (node (ref "U2") (pin "W10") (pinfunction "INIT_B_0_W10") (pintype "passive"))
    )
    (net (code "203") (name "Net-(U2I-M0_0)") (class "Default")
      (node (ref "R36") (pin "1") (pintype "passive"))
      (node (ref "U2") (pin "AA10") (pinfunction "M0_0_AA10") (pintype "passive"))
    )
    (net (code "204") (name "Net-(U2I-POR_OVERRIDE)") (class "Default")
      (node (ref "R4") (pin "1") (pintype "passive"))
      (node (ref "U2") (pin "Y12") (pinfunction "POR_OVERRIDE_Y12") (pintype "passive"))
    )
    (net (code "205") (name "Net-(U2I-PUDC_B_0)") (class "Default")
      (node (ref "R2") (pin "1") (pintype "passive"))
      (node (ref "U2") (pin "W9") (pinfunction "PUDC_B_0_W9") (pintype "passive"))
    )
    (net (code "206") (name "Net-(U3-CLK)") (class "Default")
      (node (ref "R34") (pin "1") (pintype "passive"))
      (node (ref "U3") (pin "6") (pinfunction "CLK_6") (pintype "passive"))
    )
    (net (code "207") (name "Net-(Y1-OUT+)") (class "Default")
      (node (ref "C119") (pin "1") (pinfunction "1_1") (pintype "passive"))
      (node (ref "Y1") (pin "4") (pinfunction "OUT+_4") (pintype "passive"))
    )
    (net (code "208") (name "Net-(Y1-OUT-)") (class "Default")
      (node (ref "C118") (pin "1") (pinfunction "1_1") (pintype "passive"))
      (node (ref "Y1") (pin "5") (pinfunction "OUT-_5") (pintype "passive"))
    )
    (net (code "209") (name "Net-(Y2-OUT)") (class "Default")
      (node (ref "R35") (pin "1") (pintype "passive"))
      (node (ref "Y2") (pin "3") (pinfunction "OUT_3") (pintype "passive"))
    )
    (net (code "210") (name "Net-(Y3-OUT)") (class "Default")
      (node (ref "C121") (pin "2") (pinfunction "2_2") (pintype "passive"))
      (node (ref "Y3") (pin "3") (pinfunction "OUT_3") (pintype "passive"))
    )
    (net (code "211") (name "VDD1.2") (class "Default")
      (node (ref "R52") (pin "1") (pintype "passive"))
      (node (ref "R53") (pin "1") (pintype "passive"))
    )
    (net (code "212") (name "VDD1.8") (class "Default")
      (node (ref "C62") (pin "1") (pinfunction "1_1") (pintype "passive"))
      (node (ref "J4") (pin "8") (pinfunction "8_8") (pintype "passive"))
      (node (ref "R2") (pin "2") (pintype "passive"))
      (node (ref "R31") (pin "2") (pintype "passive"))
      (node (ref "R32") (pin "2") (pintype "passive"))
      (node (ref "R33") (pin "1") (pintype "passive"))
      (node (ref "R36") (pin "2") (pintype "passive"))
      (node (ref "R37") (pin "2") (pintype "passive"))
      (node (ref "R41") (pin "2") (pintype "passive"))
      (node (ref "R42") (pin "2") (pintype "passive"))
      (node (ref "R56") (pin "1") (pintype "passive"))
      (node (ref "U3") (pin "8") (pinfunction "VCC_8") (pintype "passive"))
    )
    (net (code "213") (name "VDD3.3") (class "Default")
      (node (ref "C115") (pin "1") (pinfunction "1_1") (pintype "passive"))
      (node (ref "C120") (pin "1") (pinfunction "1_1") (pintype "passive"))
      (node (ref "C28") (pin "1") (pinfunction "1_1") (pintype "passive"))
      (node (ref "J1") (pin "15") (pinfunction "15_15") (pintype "passive"))
      (node (ref "J1") (pin "16") (pinfunction "16_16") (pintype "passive"))
      (node (ref "R38") (pin "2") (pintype "passive"))
      (node (ref "R39") (pin "2") (pintype "passive"))
      (node (ref "R40") (pin "2") (pintype "passive"))
      (node (ref "Y1") (pin "1") (pinfunction "OE_1") (pintype "passive"))
      (node (ref "Y1") (pin "6") (pinfunction "VDD_6") (pintype "passive"))
      (node (ref "Y2") (pin "4") (pinfunction "VDD_4") (pintype "passive"))
      (node (ref "Y3") (pin "4") (pinfunction "VDD_4") (pintype "passive"))
    )
    (net (code "214") (name "VDD12") (class "Default")
      (node (ref "J1") (pin "10") (pinfunction "10_10") (pintype "passive"))
      (node (ref "J1") (pin "11") (pinfunction "11_11") (pintype "passive"))
      (node (ref "J1") (pin "12") (pinfunction "12_12") (pintype "passive"))
      (node (ref "J1") (pin "7") (pinfunction "7_7") (pintype "passive"))
      (node (ref "J1") (pin "8") (pinfunction "8_8") (pintype "passive"))
      (node (ref "J1") (pin "9") (pinfunction "9_9") (pintype "passive"))
    )
    (net (code "215") (name "unconnected-(J1-Pad17)") (class "Default")
      (node (ref "J1") (pin "17") (pinfunction "17_17") (pintype "passive"))
    )
    (net (code "216") (name "unconnected-(J1-Pad18)") (class "Default")
      (node (ref "J1") (pin "18") (pinfunction "18_18") (pintype "passive"))
    )
    (net (code "217") (name "unconnected-(J1-Pad19)") (class "Default")
      (node (ref "J1") (pin "19") (pinfunction "19_19") (pintype "passive"))
    )
    (net (code "218") (name "unconnected-(J1-Pad20)") (class "Default")
      (node (ref "J1") (pin "20") (pinfunction "20_20") (pintype "passive"))
    )
    (net (code "219") (name "unconnected-(J1-Pad21)") (class "Default")
      (node (ref "J1") (pin "21") (pinfunction "21_21") (pintype "passive"))
    )
    (net (code "220") (name "unconnected-(J1-Pad22)") (class "Default")
      (node (ref "J1") (pin "22") (pinfunction "22_22") (pintype "passive"))
    )
    (net (code "221") (name "unconnected-(J1-Pad23)") (class "Default")
      (node (ref "J1") (pin "23") (pinfunction "23_23") (pintype "passive"))
    )
    (net (code "222") (name "unconnected-(J1-Pad24)") (class "Default")
      (node (ref "J1") (pin "24") (pinfunction "24_24") (pintype "passive"))
    )
    (net (code "223") (name "unconnected-(J1-Pad79)") (class "Default")
      (node (ref "J1") (pin "79") (pinfunction "79_79") (pintype "passive"))
    )
    (net (code "224") (name "unconnected-(J1-Pad80)") (class "Default")
      (node (ref "J1") (pin "80") (pinfunction "80_80") (pintype "passive"))
    )
    (net (code "225") (name "unconnected-(J1-Pad81)") (class "Default")
      (node (ref "J1") (pin "81") (pinfunction "81_81") (pintype "passive"))
    )
    (net (code "226") (name "unconnected-(J1-Pad82)") (class "Default")
      (node (ref "J1") (pin "82") (pinfunction "82_82") (pintype "passive"))
    )
    (net (code "227") (name "unconnected-(J1-Pad83)") (class "Default")
      (node (ref "J1") (pin "83") (pinfunction "83_83") (pintype "passive"))
    )
    (net (code "228") (name "unconnected-(J1-Pad84)") (class "Default")
      (node (ref "J1") (pin "84") (pinfunction "84_84") (pintype "passive"))
    )
    (net (code "229") (name "unconnected-(J1-Pad85)") (class "Default")
      (node (ref "J1") (pin "85") (pinfunction "85_85") (pintype "passive"))
    )
    (net (code "230") (name "unconnected-(J1-Pad86)") (class "Default")
      (node (ref "J1") (pin "86") (pinfunction "86_86") (pintype "passive"))
    )
    (net (code "231") (name "unconnected-(J1-Pad87)") (class "Default")
      (node (ref "J1") (pin "87") (pinfunction "87_87") (pintype "passive"))
    )
    (net (code "232") (name "unconnected-(J1-Pad88)") (class "Default")
      (node (ref "J1") (pin "88") (pinfunction "88_88") (pintype "passive"))
    )
    (net (code "233") (name "unconnected-(J1-Pad89)") (class "Default")
      (node (ref "J1") (pin "89") (pinfunction "89_89") (pintype "passive"))
    )
    (net (code "234") (name "unconnected-(J1-Pad90)") (class "Default")
      (node (ref "J1") (pin "90") (pinfunction "90_90") (pintype "passive"))
    )
    (net (code "235") (name "unconnected-(J1-Pad91)") (class "Default")
      (node (ref "J1") (pin "91") (pinfunction "91_91") (pintype "passive"))
    )
    (net (code "236") (name "unconnected-(J1-Pad92)") (class "Default")
      (node (ref "J1") (pin "92") (pinfunction "92_92") (pintype "passive"))
    )
    (net (code "237") (name "unconnected-(J1-Pad93)") (class "Default")
      (node (ref "J1") (pin "93") (pinfunction "93_93") (pintype "passive"))
    )
    (net (code "238") (name "unconnected-(J1-Pad94)") (class "Default")
      (node (ref "J1") (pin "94") (pinfunction "94_94") (pintype "passive"))
    )
    (net (code "239") (name "unconnected-(J1-Pad95)") (class "Default")
      (node (ref "J1") (pin "95") (pinfunction "95_95") (pintype "passive"))
    )
    (net (code "240") (name "unconnected-(J1-Pad96)") (class "Default")
      (node (ref "J1") (pin "96") (pinfunction "96_96") (pintype "passive"))
    )
    (net (code "241") (name "unconnected-(J1-Pad97)") (class "Default")
      (node (ref "J1") (pin "97") (pinfunction "97_97") (pintype "passive"))
    )
    (net (code "242") (name "unconnected-(J1-Pad98)") (class "Default")
      (node (ref "J1") (pin "98") (pinfunction "98_98") (pintype "passive"))
    )
    (net (code "243") (name "unconnected-(J1-Pad99)") (class "Default")
      (node (ref "J1") (pin "99") (pinfunction "99_99") (pintype "passive"))
    )
    (net (code "244") (name "unconnected-(J1-Pad100)") (class "Default")
      (node (ref "J1") (pin "100") (pinfunction "100_100") (pintype "passive"))
    )
    (net (code "245") (name "unconnected-(J2-Pad1)") (class "Default")
      (node (ref "J2") (pin "1") (pinfunction "1_1") (pintype "passive"))
    )
    (net (code "246") (name "unconnected-(J2-Pad2)") (class "Default")
      (node (ref "J2") (pin "2") (pinfunction "2_2") (pintype "passive"))
    )
    (net (code "247") (name "unconnected-(J2-Pad3)") (class "Default")
      (node (ref "J2") (pin "3") (pinfunction "3_3") (pintype "passive"))
    )
    (net (code "248") (name "unconnected-(J2-Pad4)") (class "Default")
      (node (ref "J2") (pin "4") (pinfunction "4_4") (pintype "passive"))
    )
    (net (code "249") (name "unconnected-(J2-Pad5)") (class "Default")
      (node (ref "J2") (pin "5") (pinfunction "5_5") (pintype "passive"))
    )
    (net (code "250") (name "unconnected-(J2-Pad6)") (class "Default")
      (node (ref "J2") (pin "6") (pinfunction "6_6") (pintype "passive"))
    )
    (net (code "251") (name "unconnected-(J2-Pad7)") (class "Default")
      (node (ref "J2") (pin "7") (pinfunction "7_7") (pintype "passive"))
    )
    (net (code "252") (name "unconnected-(J2-Pad8)") (class "Default")
      (node (ref "J2") (pin "8") (pinfunction "8_8") (pintype "passive"))
    )
    (net (code "253") (name "unconnected-(J2-Pad9)") (class "Default")
      (node (ref "J2") (pin "9") (pinfunction "9_9") (pintype "passive"))
    )
    (net (code "254") (name "unconnected-(J2-Pad10)") (class "Default")
      (node (ref "J2") (pin "10") (pinfunction "10_10") (pintype "passive"))
    )
    (net (code "255") (name "unconnected-(J2-Pad11)") (class "Default")
      (node (ref "J2") (pin "11") (pinfunction "11_11") (pintype "passive"))
    )
    (net (code "256") (name "unconnected-(J2-Pad12)") (class "Default")
      (node (ref "J2") (pin "12") (pinfunction "12_12") (pintype "passive"))
    )
    (net (code "257") (name "unconnected-(J2-Pad13)") (class "Default")
      (node (ref "J2") (pin "13") (pinfunction "13_13") (pintype "passive"))
    )
    (net (code "258") (name "unconnected-(J2-Pad14)") (class "Default")
      (node (ref "J2") (pin "14") (pinfunction "14_14") (pintype "passive"))
    )
    (net (code "259") (name "unconnected-(J2-Pad15)") (class "Default")
      (node (ref "J2") (pin "15") (pinfunction "15_15") (pintype "passive"))
    )
    (net (code "260") (name "unconnected-(J2-Pad16)") (class "Default")
      (node (ref "J2") (pin "16") (pinfunction "16_16") (pintype "passive"))
    )
    (net (code "261") (name "unconnected-(J2-Pad17)") (class "Default")
      (node (ref "J2") (pin "17") (pinfunction "17_17") (pintype "passive"))
    )
    (net (code "262") (name "unconnected-(J2-Pad18)") (class "Default")
      (node (ref "J2") (pin "18") (pinfunction "18_18") (pintype "passive"))
    )
    (net (code "263") (name "unconnected-(J2-Pad85)") (class "Default")
      (node (ref "J2") (pin "85") (pinfunction "85_85") (pintype "passive"))
    )
    (net (code "264") (name "unconnected-(J2-Pad87)") (class "Default")
      (node (ref "J2") (pin "87") (pinfunction "87_87") (pintype "passive"))
    )
    (net (code "265") (name "unconnected-(J2-Pad88)") (class "Default")
      (node (ref "J2") (pin "88") (pinfunction "88_88") (pintype "passive"))
    )
    (net (code "266") (name "unconnected-(J2-Pad89)") (class "Default")
      (node (ref "J2") (pin "89") (pinfunction "89_89") (pintype "passive"))
    )
    (net (code "267") (name "unconnected-(J2-Pad90)") (class "Default")
      (node (ref "J2") (pin "90") (pinfunction "90_90") (pintype "passive"))
    )
    (net (code "268") (name "unconnected-(J2-Pad91)") (class "Default")
      (node (ref "J2") (pin "91") (pinfunction "91_91") (pintype "passive"))
    )
    (net (code "269") (name "unconnected-(J2-Pad92)") (class "Default")
      (node (ref "J2") (pin "92") (pinfunction "92_92") (pintype "passive"))
    )
    (net (code "270") (name "unconnected-(J2-Pad93)") (class "Default")
      (node (ref "J2") (pin "93") (pinfunction "93_93") (pintype "passive"))
    )
    (net (code "271") (name "unconnected-(J2-Pad94)") (class "Default")
      (node (ref "J2") (pin "94") (pinfunction "94_94") (pintype "passive"))
    )
    (net (code "272") (name "unconnected-(J2-Pad95)") (class "Default")
      (node (ref "J2") (pin "95") (pinfunction "95_95") (pintype "passive"))
    )
    (net (code "273") (name "unconnected-(J2-Pad96)") (class "Default")
      (node (ref "J2") (pin "96") (pinfunction "96_96") (pintype "passive"))
    )
    (net (code "274") (name "unconnected-(J2-Pad97)") (class "Default")
      (node (ref "J2") (pin "97") (pinfunction "97_97") (pintype "passive"))
    )
    (net (code "275") (name "unconnected-(J2-Pad98)") (class "Default")
      (node (ref "J2") (pin "98") (pinfunction "98_98") (pintype "passive"))
    )
    (net (code "276") (name "unconnected-(J2-Pad99)") (class "Default")
      (node (ref "J2") (pin "99") (pinfunction "99_99") (pintype "passive"))
    )
    (net (code "277") (name "unconnected-(J2-Pad100)") (class "Default")
      (node (ref "J2") (pin "100") (pinfunction "100_100") (pintype "passive"))
    )
    (net (code "278") (name "unconnected-(J3-Pad5)") (class "Default")
      (node (ref "J3") (pin "5") (pinfunction "5_5") (pintype "passive"))
    )
    (net (code "279") (name "unconnected-(J3-Pad6)") (class "Default")
      (node (ref "J3") (pin "6") (pinfunction "6_6") (pintype "passive"))
    )
    (net (code "280") (name "unconnected-(J3-Pad7)") (class "Default")
      (node (ref "J3") (pin "7") (pinfunction "7_7") (pintype "passive"))
    )
    (net (code "281") (name "unconnected-(J3-Pad8)") (class "Default")
      (node (ref "J3") (pin "8") (pinfunction "8_8") (pintype "passive"))
    )
    (net (code "282") (name "unconnected-(J3-Pad9)") (class "Default")
      (node (ref "J3") (pin "9") (pinfunction "9_9") (pintype "passive"))
    )
    (net (code "283") (name "unconnected-(J3-Pad10)") (class "Default")
      (node (ref "J3") (pin "10") (pinfunction "10_10") (pintype "passive"))
    )
    (net (code "284") (name "unconnected-(J3-Pad11)") (class "Default")
      (node (ref "J3") (pin "11") (pinfunction "11_11") (pintype "passive"))
    )
    (net (code "285") (name "unconnected-(J3-Pad12)") (class "Default")
      (node (ref "J3") (pin "12") (pinfunction "12_12") (pintype "passive"))
    )
    (net (code "286") (name "unconnected-(J3-Pad13)") (class "Default")
      (node (ref "J3") (pin "13") (pinfunction "13_13") (pintype "passive"))
    )
    (net (code "287") (name "unconnected-(J3-Pad14)") (class "Default")
      (node (ref "J3") (pin "14") (pinfunction "14_14") (pintype "passive"))
    )
    (net (code "288") (name "unconnected-(J3-Pad15)") (class "Default")
      (node (ref "J3") (pin "15") (pinfunction "15_15") (pintype "passive"))
    )
    (net (code "289") (name "unconnected-(J3-Pad16)") (class "Default")
      (node (ref "J3") (pin "16") (pinfunction "16_16") (pintype "passive"))
    )
    (net (code "290") (name "unconnected-(J3-Pad17)") (class "Default")
      (node (ref "J3") (pin "17") (pinfunction "17_17") (pintype "passive"))
    )
    (net (code "291") (name "unconnected-(J3-Pad18)") (class "Default")
      (node (ref "J3") (pin "18") (pinfunction "18_18") (pintype "passive"))
    )
    (net (code "292") (name "unconnected-(J3-Pad19)") (class "Default")
      (node (ref "J3") (pin "19") (pinfunction "19_19") (pintype "passive"))
    )
    (net (code "293") (name "unconnected-(J3-Pad20)") (class "Default")
      (node (ref "J3") (pin "20") (pinfunction "20_20") (pintype "passive"))
    )
    (net (code "294") (name "unconnected-(J3-Pad83)") (class "Default")
      (node (ref "J3") (pin "83") (pinfunction "83_83") (pintype "passive"))
    )
    (net (code "295") (name "unconnected-(J3-Pad84)") (class "Default")
      (node (ref "J3") (pin "84") (pinfunction "84_84") (pintype "passive"))
    )
    (net (code "296") (name "unconnected-(J3-Pad85)") (class "Default")
      (node (ref "J3") (pin "85") (pinfunction "85_85") (pintype "passive"))
    )
    (net (code "297") (name "unconnected-(J3-Pad86)") (class "Default")
      (node (ref "J3") (pin "86") (pinfunction "86_86") (pintype "passive"))
    )
    (net (code "298") (name "unconnected-(J3-Pad87)") (class "Default")
      (node (ref "J3") (pin "87") (pinfunction "87_87") (pintype "passive"))
    )
    (net (code "299") (name "unconnected-(J3-Pad88)") (class "Default")
      (node (ref "J3") (pin "88") (pinfunction "88_88") (pintype "passive"))
    )
    (net (code "300") (name "unconnected-(J3-Pad89)") (class "Default")
      (node (ref "J3") (pin "89") (pinfunction "89_89") (pintype "passive"))
    )
    (net (code "301") (name "unconnected-(J3-Pad90)") (class "Default")
      (node (ref "J3") (pin "90") (pinfunction "90_90") (pintype "passive"))
    )
    (net (code "302") (name "unconnected-(J3-Pad91)") (class "Default")
      (node (ref "J3") (pin "91") (pinfunction "91_91") (pintype "passive"))
    )
    (net (code "303") (name "unconnected-(J3-Pad92)") (class "Default")
      (node (ref "J3") (pin "92") (pinfunction "92_92") (pintype "passive"))
    )
    (net (code "304") (name "unconnected-(J3-Pad93)") (class "Default")
      (node (ref "J3") (pin "93") (pinfunction "93_93") (pintype "passive"))
    )
    (net (code "305") (name "unconnected-(J3-Pad94)") (class "Default")
      (node (ref "J3") (pin "94") (pinfunction "94_94") (pintype "passive"))
    )
    (net (code "306") (name "unconnected-(J3-Pad95)") (class "Default")
      (node (ref "J3") (pin "95") (pinfunction "95_95") (pintype "passive"))
    )
    (net (code "307") (name "unconnected-(J3-Pad96)") (class "Default")
      (node (ref "J3") (pin "96") (pinfunction "96_96") (pintype "passive"))
    )
    (net (code "308") (name "unconnected-(J3-Pad97)") (class "Default")
      (node (ref "J3") (pin "97") (pinfunction "97_97") (pintype "passive"))
    )
    (net (code "309") (name "unconnected-(J3-Pad98)") (class "Default")
      (node (ref "J3") (pin "98") (pinfunction "98_98") (pintype "passive"))
    )
    (net (code "310") (name "unconnected-(J3-Pad99)") (class "Default")
      (node (ref "J3") (pin "99") (pinfunction "99_99") (pintype "passive"))
    )
    (net (code "311") (name "unconnected-(J3-Pad100)") (class "Default")
      (node (ref "J3") (pin "100") (pinfunction "100_100") (pintype "passive"))
    )
    (net (code "312") (name "unconnected-(J4-Pad13)") (class "Default")
      (node (ref "J4") (pin "13") (pinfunction "13_13") (pintype "passive"))
    )
    (net (code "313") (name "unconnected-(J4-Pad14)") (class "Default")
      (node (ref "J4") (pin "14") (pinfunction "14_14") (pintype "passive"))
    )
    (net (code "314") (name "unconnected-(Y1-NC-Pad2)") (class "Default")
      (node (ref "Y1") (pin "2") (pinfunction "NC_2") (pintype "passive+no_connect"))
    )
    (net (code "315") (name "unconnected-(Y2-NC-Pad1)") (class "Default")
      (node (ref "Y2") (pin "1") (pinfunction "NC_1") (pintype "passive+no_connect"))
    )
    (net (code "316") (name "unconnected-(Y3-NC-Pad1)") (class "Default")
      (node (ref "Y3") (pin "1") (pinfunction "NC_1") (pintype "passive+no_connect"))
    )
  )
)
